# bletka.net
KiCad netlist of a schematic drawn in EAGLE
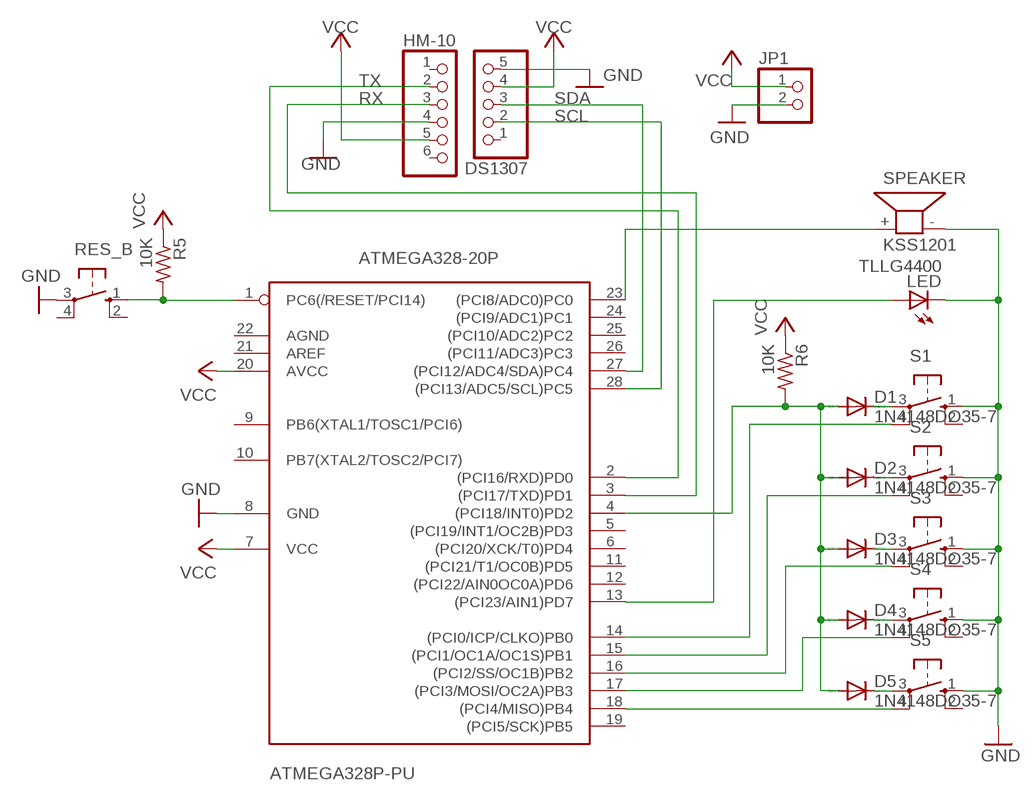
[diagram p0: schematic, sheet 1]

(export (version "E")
  (design (tool "Eeschema 10.0.6"))
  (components
    (comp (ref "ATMEGA328P-PU")
      (value "ATMEGA328-20P")
      (footprint "eagle-import:DIL28-3")
      (libsource (lib "eagle-import") (part "ATMEGA328P-20"))
    )
    (comp (ref "D1")
      (value "1N4148DO35-7")
      (footprint "eagle-import:DO35-7")
      (libsource (lib "eagle-import") (part "1N4148DO35-7"))
    )
    (comp (ref "D2")
      (value "1N4148DO35-7")
      (footprint "eagle-import:DO35-7")
      (libsource (lib "eagle-import") (part "1N4148DO35-7"))
    )
    (comp (ref "D3")
      (value "1N4148DO35-7")
      (footprint "eagle-import:DO35-7")
      (libsource (lib "eagle-import") (part "1N4148DO35-7"))
    )
    (comp (ref "D4")
      (value "1N4148DO35-7")
      (footprint "eagle-import:DO35-7")
      (libsource (lib "eagle-import") (part "1N4148DO35-7"))
    )
    (comp (ref "D5")
      (value "1N4148DO35-7")
      (footprint "eagle-import:DO35-7")
      (libsource (lib "eagle-import") (part "1N4148DO35-7"))
    )
    (comp (ref "DS1307")
      (value "PINHD-1X5")
      (footprint "eagle-import:1X05")
      (libsource (lib "eagle-import") (part "PINHD-1X5"))
    )
    (comp (ref "HM-10")
      (value "PINHD-1X6")
      (footprint "eagle-import:1X06")
      (libsource (lib "eagle-import") (part "PINHD-1X6"))
    )
    (comp (ref "JP1")
      (value "PINHD-1X2")
      (footprint "eagle-import:1X02")
      (libsource (lib "eagle-import") (part "PINHD-1X2"))
    )
    (comp (ref "LED")
      (value "TLLG4400")
      (footprint "eagle-import:LED3MM")
      (fields (field (name "MF") "VISHAY SEMICONDUCTOR"))
      (libsource (lib "eagle-import") (part "TLLG4400"))
    )
    (comp (ref "R5")
      (value "10K")
      (footprint "eagle-import:0207_10")
      (libsource (lib "eagle-import") (part "R-US_0207/10"))
    )
    (comp (ref "R6")
      (value "10K")
      (footprint "eagle-import:0207_10")
      (libsource (lib "eagle-import") (part "R-US_0207/10"))
    )
    (comp (ref "RES_B")
      (value "10-XX")
      (footprint "eagle-import:B3F-10XX")
      (fields (field (name "MPN") "B3F-1000"))
      (libsource (lib "eagle-import") (part "10-XX"))
    )
    (comp (ref "S1")
      (value "10-XX")
      (footprint "eagle-import:B3F-10XX")
      (fields (field (name "MPN") "B3F-1000"))
      (libsource (lib "eagle-import") (part "10-XX"))
    )
    (comp (ref "S2")
      (value "10-XX")
      (footprint "eagle-import:B3F-10XX")
      (fields (field (name "MPN") "B3F-1000"))
      (libsource (lib "eagle-import") (part "10-XX"))
    )
    (comp (ref "S3")
      (value "10-XX")
      (footprint "eagle-import:B3F-10XX")
      (fields (field (name "MPN") "B3F-1000"))
      (libsource (lib "eagle-import") (part "10-XX"))
    )
    (comp (ref "S4")
      (value "10-XX")
      (footprint "eagle-import:B3F-10XX")
      (fields (field (name "MPN") "B3F-1000"))
      (libsource (lib "eagle-import") (part "10-XX"))
    )
    (comp (ref "S5")
      (value "10-XX")
      (footprint "eagle-import:B3F-10XX")
      (fields (field (name "MPN") "B3F-1000"))
      (libsource (lib "eagle-import") (part "10-XX"))
    )
    (comp (ref "SPEAKER")
      (value "KSS1201")
      (footprint "eagle-import:KSS1201")
      (libsource (lib "eagle-import") (part "KSS1201"))
    )
  )
  (nets
    (net (code "1") (name "/RX") (class "Default")
      (node (ref "ATMEGA328P-PU") (pin "3") (pinfunction "(PCI17/TXD)PD1_3") (pintype "bidirectional"))
      (node (ref "HM-10") (pin "3") (pinfunction "3_3") (pintype "passive"))
    )
    (net (code "2") (name "/SCL") (class "Default")
      (node (ref "ATMEGA328P-PU") (pin "28") (pinfunction "(PCI13/ADC5/SCL)PC5_28") (pintype "bidirectional"))
      (node (ref "DS1307") (pin "2") (pinfunction "2_2") (pintype "passive"))
    )
    (net (code "3") (name "/SDA") (class "Default")
      (node (ref "ATMEGA328P-PU") (pin "27") (pinfunction "(PCI12/ADC4/SDA)PC4_27") (pintype "bidirectional"))
      (node (ref "DS1307") (pin "3") (pinfunction "3_3") (pintype "passive"))
    )
    (net (code "4") (name "/TX") (class "Default")
      (node (ref "ATMEGA328P-PU") (pin "2") (pinfunction "(PCI16/RXD)PD0_2") (pintype "bidirectional"))
      (node (ref "HM-10") (pin "2") (pinfunction "2_2") (pintype "passive"))
    )
    (net (code "5") (name "GND") (class "Default")
      (node (ref "ATMEGA328P-PU") (pin "8") (pinfunction "GND_8") (pintype "bidirectional"))
      (node (ref "DS1307") (pin "5") (pinfunction "5_5") (pintype "passive"))
      (node (ref "HM-10") (pin "4") (pinfunction "4_4") (pintype "passive"))
      (node (ref "JP1") (pin "2") (pinfunction "2_2") (pintype "passive"))
      (node (ref "LED") (pin "K") (pinfunction "C_K") (pintype "passive"))
      (node (ref "RES_B") (pin "3") (pinfunction "P_3") (pintype "passive"))
      (node (ref "S1") (pin "1") (pinfunction "S_1") (pintype "passive"))
      (node (ref "S2") (pin "1") (pinfunction "S_1") (pintype "passive"))
      (node (ref "S3") (pin "1") (pinfunction "S_1") (pintype "passive"))
      (node (ref "S4") (pin "1") (pinfunction "S_1") (pintype "passive"))
      (node (ref "S5") (pin "1") (pinfunction "S_1") (pintype "passive"))
      (node (ref "SPEAKER") (pin "-") (pinfunction "2_-") (pintype "passive"))
    )
    (net (code "6") (name "Net-(ATMEGA328P-PU-(PCI0{slash}ICP{slash}CLKO)PB0)") (class "Default")
      (node (ref "ATMEGA328P-PU") (pin "14") (pinfunction "(PCI0/ICP/CLKO)PB0_14") (pintype "bidirectional"))
      (node (ref "S1") (pin "4") (pinfunction "P1_4") (pintype "passive"))
    )
    (net (code "7") (name "Net-(ATMEGA328P-PU-(PCI1{slash}OC1A{slash}OC1S)PB1)") (class "Default")
      (node (ref "ATMEGA328P-PU") (pin "15") (pinfunction "(PCI1/OC1A/OC1S)PB1_15") (pintype "bidirectional"))
      (node (ref "S2") (pin "4") (pinfunction "P1_4") (pintype "passive"))
    )
    (net (code "8") (name "Net-(ATMEGA328P-PU-(PCI2{slash}SS{slash}OC1B)PB2)") (class "Default")
      (node (ref "ATMEGA328P-PU") (pin "16") (pinfunction "(PCI2/SS/OC1B)PB2_16") (pintype "bidirectional"))
      (node (ref "S3") (pin "4") (pinfunction "P1_4") (pintype "passive"))
    )
    (net (code "9") (name "Net-(ATMEGA328P-PU-(PCI3{slash}MOSI{slash}OC2A)PB3)") (class "Default")
      (node (ref "ATMEGA328P-PU") (pin "17") (pinfunction "(PCI3/MOSI/OC2A)PB3_17") (pintype "bidirectional"))
      (node (ref "S4") (pin "4") (pinfunction "P1_4") (pintype "passive"))
    )
    (net (code "10") (name "Net-(ATMEGA328P-PU-(PCI4{slash}MISO)PB4)") (class "Default")
      (node (ref "ATMEGA328P-PU") (pin "18") (pinfunction "(PCI4/MISO)PB4_18") (pintype "bidirectional"))
      (node (ref "S5") (pin "4") (pinfunction "P1_4") (pintype "passive"))
    )
    (net (code "11") (name "Net-(ATMEGA328P-PU-(PCI8{slash}ADC0)PC0)") (class "Default")
      (node (ref "ATMEGA328P-PU") (pin "23") (pinfunction "(PCI8/ADC0)PC0_23") (pintype "bidirectional"))
      (node (ref "SPEAKER") (pin "+") (pinfunction "1_+") (pintype "passive"))
    )
    (net (code "12") (name "Net-(ATMEGA328P-PU-(PCI18{slash}INT0)PD2)") (class "Default")
      (node (ref "ATMEGA328P-PU") (pin "4") (pinfunction "(PCI18/INT0)PD2_4") (pintype "bidirectional"))
      (node (ref "D1") (pin "A") (pinfunction "A_A") (pintype "passive"))
      (node (ref "D2") (pin "A") (pinfunction "A_A") (pintype "passive"))
      (node (ref "D3") (pin "A") (pinfunction "A_A") (pintype "passive"))
      (node (ref "D4") (pin "A") (pinfunction "A_A") (pintype "passive"))
      (node (ref "D5") (pin "A") (pinfunction "A_A") (pintype "passive"))
      (node (ref "R6") (pin "2") (pinfunction "2_2") (pintype "passive"))
    )
    (net (code "13") (name "Net-(ATMEGA328P-PU-(PCI23{slash}AIN1)PD7)") (class "Default")
      (node (ref "ATMEGA328P-PU") (pin "13") (pinfunction "(PCI23/AIN1)PD7_13") (pintype "bidirectional"))
      (node (ref "LED") (pin "A") (pinfunction "A_A") (pintype "passive"))
    )
    (net (code "14") (name "Net-(ATMEGA328P-PU-PC6({slash}RESET{slash}PCI14))") (class "Default")
      (node (ref "ATMEGA328P-PU") (pin "1") (pinfunction "PC6(/RESET/PCI14)_1") (pintype "bidirectional"))
      (node (ref "R5") (pin "2") (pinfunction "2_2") (pintype "passive"))
      (node (ref "RES_B") (pin "1") (pinfunction "S_1") (pintype "passive"))
    )
    (net (code "15") (name "Net-(S1-P)") (class "Default")
      (node (ref "D1") (pin "C") (pinfunction "C_C") (pintype "passive"))
      (node (ref "S1") (pin "3") (pinfunction "P_3") (pintype "passive"))
    )
    (net (code "16") (name "Net-(S2-P)") (class "Default")
      (node (ref "D2") (pin "C") (pinfunction "C_C") (pintype "passive"))
      (node (ref "S2") (pin "3") (pinfunction "P_3") (pintype "passive"))
    )
    (net (code "17") (name "Net-(S3-P)") (class "Default")
      (node (ref "D3") (pin "C") (pinfunction "C_C") (pintype "passive"))
      (node (ref "S3") (pin "3") (pinfunction "P_3") (pintype "passive"))
    )
    (net (code "18") (name "Net-(S4-P)") (class "Default")
      (node (ref "D4") (pin "C") (pinfunction "C_C") (pintype "passive"))
      (node (ref "S4") (pin "3") (pinfunction "P_3") (pintype "passive"))
    )
    (net (code "19") (name "Net-(S5-P)") (class "Default")
      (node (ref "D5") (pin "C") (pinfunction "C_C") (pintype "passive"))
      (node (ref "S5") (pin "3") (pinfunction "P_3") (pintype "passive"))
    )
    (net (code "20") (name "VCC") (class "Default")
      (node (ref "ATMEGA328P-PU") (pin "20") (pinfunction "AVCC_20") (pintype "bidirectional"))
      (node (ref "ATMEGA328P-PU") (pin "7") (pinfunction "VCC_7") (pintype "bidirectional"))
      (node (ref "DS1307") (pin "4") (pinfunction "4_4") (pintype "passive"))
      (node (ref "HM-10") (pin "5") (pinfunction "5_5") (pintype "passive"))
      (node (ref "JP1") (pin "1") (pinfunction "1_1") (pintype "passive"))
      (node (ref "R5") (pin "1") (pinfunction "1_1") (pintype "passive"))
      (node (ref "R6") (pin "1") (pinfunction "1_1") (pintype "passive"))
    )
    (net (code "21") (name "unconnected-(ATMEGA328P-PU-(PCI5{slash}SCK)PB5-Pad19)") (class "Default")
      (node (ref "ATMEGA328P-PU") (pin "19") (pinfunction "(PCI5/SCK)PB5_19") (pintype "bidirectional"))
    )
    (net (code "22") (name "unconnected-(ATMEGA328P-PU-(PCI9{slash}ADC1)PC1-Pad24)") (class "Default")
      (node (ref "ATMEGA328P-PU") (pin "24") (pinfunction "(PCI9/ADC1)PC1_24") (pintype "bidirectional"))
    )
    (net (code "23") (name "unconnected-(ATMEGA328P-PU-(PCI10{slash}ADC2)PC2-Pad25)") (class "Default")
      (node (ref "ATMEGA328P-PU") (pin "25") (pinfunction "(PCI10/ADC2)PC2_25") (pintype "bidirectional"))
    )
    (net (code "24") (name "unconnected-(ATMEGA328P-PU-(PCI11{slash}ADC3)PC3-Pad26)") (class "Default")
      (node (ref "ATMEGA328P-PU") (pin "26") (pinfunction "(PCI11/ADC3)PC3_26") (pintype "bidirectional"))
    )
    (net (code "25") (name "unconnected-(ATMEGA328P-PU-(PCI19{slash}INT1{slash}OC2B)PD3-Pad5)") (class "Default")
      (node (ref "ATMEGA328P-PU") (pin "5") (pinfunction "(PCI19/INT1/OC2B)PD3_5") (pintype "bidirectional"))
    )
    (net (code "26") (name "unconnected-(ATMEGA328P-PU-(PCI20{slash}XCK{slash}T0)PD4-Pad6)") (class "Default")
      (node (ref "ATMEGA328P-PU") (pin "6") (pinfunction "(PCI20/XCK/T0)PD4_6") (pintype "bidirectional"))
    )
    (net (code "27") (name "unconnected-(ATMEGA328P-PU-(PCI21{slash}T1{slash}OC0B)PD5-Pad11)") (class "Default")
      (node (ref "ATMEGA328P-PU") (pin "11") (pinfunction "(PCI21/T1/OC0B)PD5_11") (pintype "bidirectional"))
    )
    (net (code "28") (name "unconnected-(ATMEGA328P-PU-(PCI22{slash}AIN0OC0A)PD6-Pad12)") (class "Default")
      (node (ref "ATMEGA328P-PU") (pin "12") (pinfunction "(PCI22/AIN0OC0A)PD6_12") (pintype "bidirectional"))
    )
    (net (code "29") (name "unconnected-(ATMEGA328P-PU-AGND-Pad22)") (class "Default")
      (node (ref "ATMEGA328P-PU") (pin "22") (pinfunction "AGND_22") (pintype "bidirectional"))
    )
    (net (code "30") (name "unconnected-(ATMEGA328P-PU-AREF-Pad21)") (class "Default")
      (node (ref "ATMEGA328P-PU") (pin "21") (pinfunction "AREF_21") (pintype "bidirectional"))
    )
    (net (code "31") (name "unconnected-(ATMEGA328P-PU-PB6(XTAL1{slash}TOSC1{slash}PCI6)-Pad9)") (class "Default")
      (node (ref "ATMEGA328P-PU") (pin "9") (pinfunction "PB6(XTAL1/TOSC1/PCI6)_9") (pintype "bidirectional"))
    )
    (net (code "32") (name "unconnected-(ATMEGA328P-PU-PB7(XTAL2{slash}TOSC2{slash}PCI7)-Pad10)") (class "Default")
      (node (ref "ATMEGA328P-PU") (pin "10") (pinfunction "PB7(XTAL2/TOSC2/PCI7)_10") (pintype "bidirectional"))
    )
    (net (code "33") (name "unconnected-(DS1307-Pad1)") (class "Default")
      (node (ref "DS1307") (pin "1") (pinfunction "1_1") (pintype "passive"))
    )
    (net (code "34") (name "unconnected-(HM-10-Pad1)") (class "Default")
      (node (ref "HM-10") (pin "1") (pinfunction "1_1") (pintype "passive"))
    )
    (net (code "35") (name "unconnected-(HM-10-Pad6)") (class "Default")
      (node (ref "HM-10") (pin "6") (pinfunction "6_6") (pintype "passive"))
    )
    (net (code "36") (name "unconnected-(RES_B-P1-Pad4)") (class "Default")
      (node (ref "RES_B") (pin "4") (pinfunction "P1_4") (pintype "passive"))
    )
    (net (code "37") (name "unconnected-(RES_B-S1-Pad2)") (class "Default")
      (node (ref "RES_B") (pin "2") (pinfunction "S1_2") (pintype "passive"))
    )
    (net (code "38") (name "unconnected-(S1-S1-Pad2)") (class "Default")
      (node (ref "S1") (pin "2") (pinfunction "S1_2") (pintype "passive"))
    )
    (net (code "39") (name "unconnected-(S2-S1-Pad2)") (class "Default")
      (node (ref "S2") (pin "2") (pinfunction "S1_2") (pintype "passive"))
    )
    (net (code "40") (name "unconnected-(S3-S1-Pad2)") (class "Default")
      (node (ref "S3") (pin "2") (pinfunction "S1_2") (pintype "passive"))
    )
    (net (code "41") (name "unconnected-(S4-S1-Pad2)") (class "Default")
      (node (ref "S4") (pin "2") (pinfunction "S1_2") (pintype "passive"))
    )
    (net (code "42") (name "unconnected-(S5-S1-Pad2)") (class "Default")
      (node (ref "S5") (pin "2") (pinfunction "S1_2") (pintype "passive"))
    )
  )
)
